# racer2.net
KiCad netlist of a schematic drawn in EAGLE
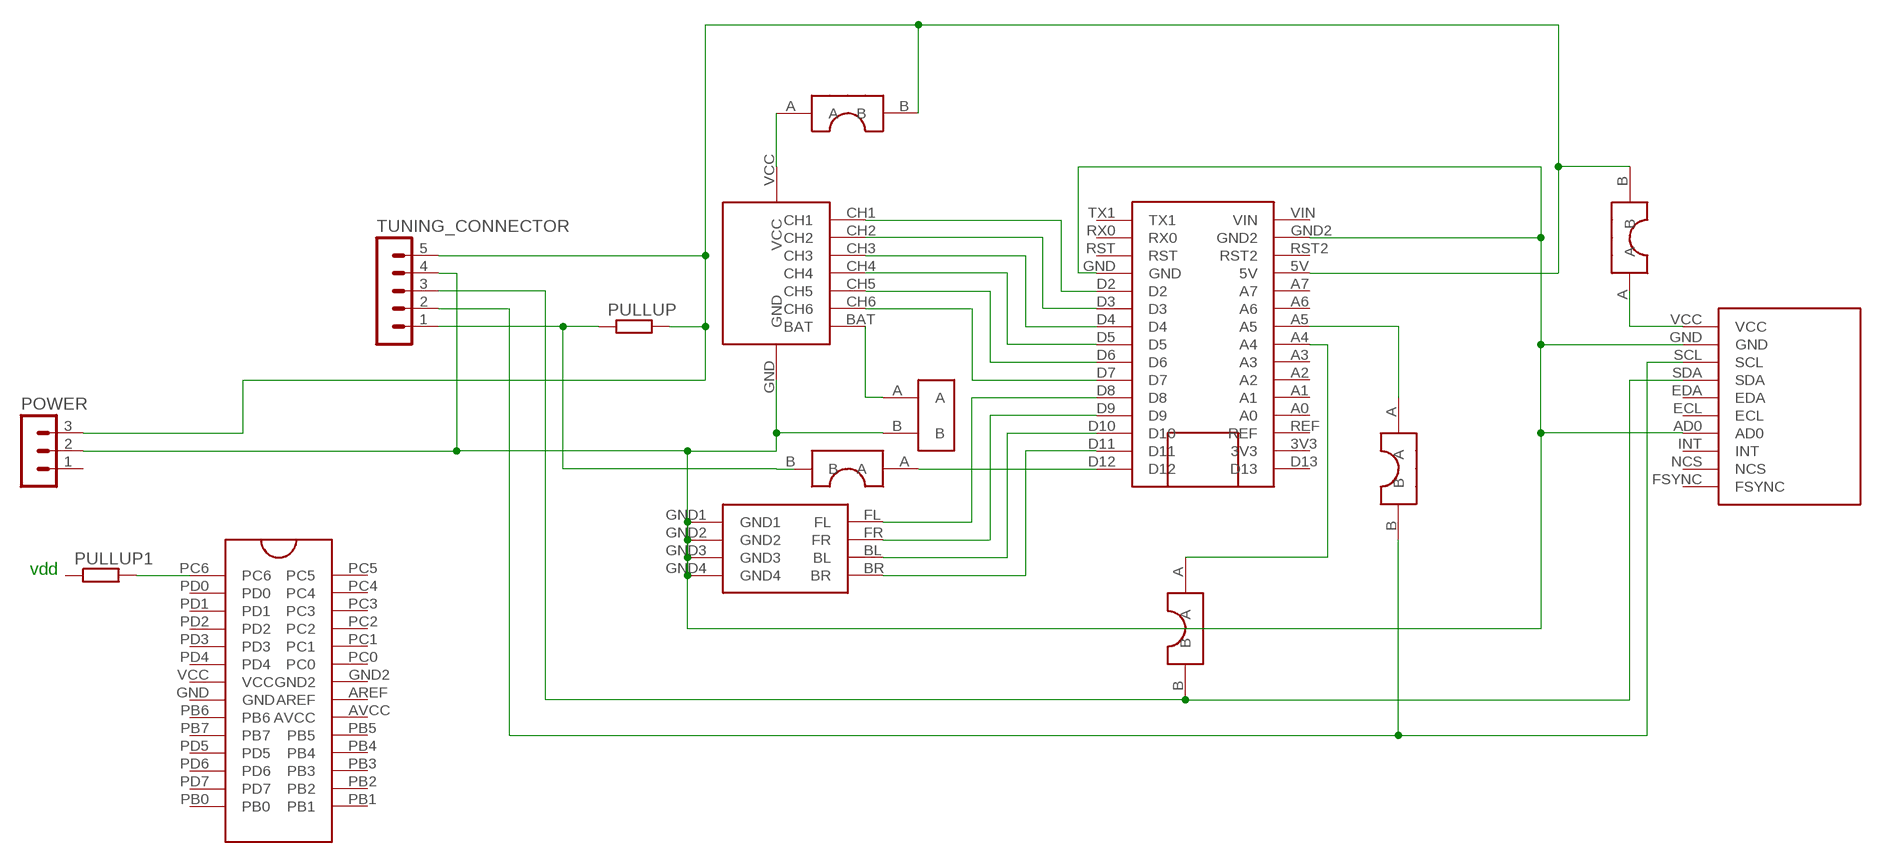
[diagram p0: schematic, sheet 1]

(export (version "E")
  (design (tool "Eeschema 10.0.6"))
  (components
    (comp (ref "POWER")
      (value "MA03-1")
      (footprint "eagle-import:MA03-1")
      (libsource (lib "eagle-import") (part "MA03-1"))
    )
    (comp (ref "PULLUP")
      (value "R0204/7")
      (footprint "eagle-import:0204_7")
      (libsource (lib "eagle-import") (part "R0204/7"))
    )
    (comp (ref "PULLUP1")
      (value "R0204/7")
      (footprint "eagle-import:0204_7")
      (libsource (lib "eagle-import") (part "R0204/7"))
    )
    (comp (ref "TUNING_CONNECTOR")
      (value "MA05-1")
      (footprint "eagle-import:MA05-1")
      (libsource (lib "eagle-import") (part "MA05-1"))
    )
    (comp (ref "U$1")
      (value "NANO")
      (footprint "eagle-import:NANO")
      (libsource (lib "eagle-import") (part "NANO"))
    )
    (comp (ref "U$2")
      (value "BUTTON_PULLUP")
      (footprint "eagle-import:BUTTON_PULLUP")
      (libsource (lib "eagle-import") (part "BUTTON_PULLUP"))
    )
    (comp (ref "U$3")
      (value "FS_RADIO")
      (footprint "eagle-import:FS_RADIO")
      (libsource (lib "eagle-import") (part "FS_RADIO"))
    )
    (comp (ref "U$4")
      (value "MPU9250")
      (footprint "eagle-import:MPU9250")
      (libsource (lib "eagle-import") (part "MPU9250"))
    )
    (comp (ref "U$5")
      (value "MOTOR_HEADER")
      (footprint "eagle-import:MOTOR_HEADER")
      (libsource (lib "eagle-import") (part "MOTOR_HEADER"))
    )
    (comp (ref "U$6")
      (value "BRIDGE")
      (footprint "eagle-import:BRIDGE")
      (libsource (lib "eagle-import") (part "BRIDGE"))
    )
    (comp (ref "U$7")
      (value "BRIDGE")
      (footprint "eagle-import:BRIDGE")
      (libsource (lib "eagle-import") (part "BRIDGE"))
    )
    (comp (ref "U$8")
      (value "BRIDGE")
      (footprint "eagle-import:BRIDGE")
      (libsource (lib "eagle-import") (part "BRIDGE"))
    )
    (comp (ref "U$9")
      (value "BRIDGE")
      (footprint "eagle-import:BRIDGE")
      (libsource (lib "eagle-import") (part "BRIDGE"))
    )
    (comp (ref "U$10")
      (value "BRIDGE")
      (footprint "eagle-import:BRIDGE")
      (libsource (lib "eagle-import") (part "BRIDGE"))
    )
    (comp (ref "U$11")
      (value "ATMEGA328P")
      (footprint "eagle-import:ATMEGA328P")
      (libsource (lib "eagle-import") (part "ATMEGA328P"))
    )
  )
  (nets
    (net (code "1") (name "Net-(POWER-Pad2)") (class "Default")
      (node (ref "POWER") (pin "2") (pinfunction "2_2") (pintype "passive"))
      (node (ref "TUNING_CONNECTOR") (pin "4") (pinfunction "4_4") (pintype "passive"))
      (node (ref "U$1") (pin "GND") (pinfunction "GND_GND") (pintype "bidirectional"))
      (node (ref "U$1") (pin "GND2") (pinfunction "GND2_GND2") (pintype "bidirectional"))
      (node (ref "U$2") (pin "B") (pinfunction "B_B") (pintype "bidirectional"))
      (node (ref "U$3") (pin "GND") (pinfunction "GND_GND") (pintype "bidirectional"))
      (node (ref "U$4") (pin "AD0") (pinfunction "AD0_AD0") (pintype "bidirectional"))
      (node (ref "U$4") (pin "GND") (pinfunction "GND_GND") (pintype "bidirectional"))
      (node (ref "U$5") (pin "GND1") (pinfunction "GND1_GND1") (pintype "bidirectional"))
      (node (ref "U$5") (pin "GND2") (pinfunction "GND2_GND2") (pintype "bidirectional"))
      (node (ref "U$5") (pin "GND3") (pinfunction "GND3_GND3") (pintype "bidirectional"))
      (node (ref "U$5") (pin "GND4") (pinfunction "GND4_GND4") (pintype "bidirectional"))
    )
    (net (code "2") (name "Net-(POWER-Pad3)") (class "Default")
      (node (ref "POWER") (pin "3") (pinfunction "3_3") (pintype "passive"))
      (node (ref "PULLUP") (pin "2") (pinfunction "2_2") (pintype "passive"))
      (node (ref "TUNING_CONNECTOR") (pin "5") (pinfunction "5_5") (pintype "passive"))
      (node (ref "U$1") (pin "5V") (pinfunction "5V_5V") (pintype "bidirectional"))
      (node (ref "U$10") (pin "B") (pinfunction "B_B") (pintype "bidirectional"))
      (node (ref "U$9") (pin "B") (pinfunction "B_B") (pintype "bidirectional"))
    )
    (net (code "3") (name "Net-(PULLUP-Pad1)") (class "Default")
      (node (ref "PULLUP") (pin "1") (pinfunction "1_1") (pintype "passive"))
      (node (ref "TUNING_CONNECTOR") (pin "1") (pinfunction "1_1") (pintype "passive"))
      (node (ref "U$8") (pin "B") (pinfunction "B_B") (pintype "bidirectional"))
    )
    (net (code "4") (name "Net-(PULLUP1-Pad2)") (class "Default")
      (node (ref "PULLUP1") (pin "2") (pinfunction "2_2") (pintype "passive"))
      (node (ref "U$11") (pin "PC6") (pinfunction "PC6_PC6") (pintype "bidirectional"))
    )
    (net (code "5") (name "Net-(TUNING_CONNECTOR-Pad2)") (class "Default")
      (node (ref "TUNING_CONNECTOR") (pin "2") (pinfunction "2_2") (pintype "passive"))
      (node (ref "U$4") (pin "SCL") (pinfunction "SCL_SCL") (pintype "bidirectional"))
      (node (ref "U$7") (pin "B") (pinfunction "B_B") (pintype "bidirectional"))
    )
    (net (code "6") (name "Net-(TUNING_CONNECTOR-Pad3)") (class "Default")
      (node (ref "TUNING_CONNECTOR") (pin "3") (pinfunction "3_3") (pintype "passive"))
      (node (ref "U$4") (pin "SDA") (pinfunction "SDA_SDA") (pintype "bidirectional"))
      (node (ref "U$6") (pin "B") (pinfunction "B_B") (pintype "bidirectional"))
    )
    (net (code "7") (name "Net-(U$1-PadA4)") (class "Default")
      (node (ref "U$1") (pin "A4") (pinfunction "A4_A4") (pintype "bidirectional"))
      (node (ref "U$6") (pin "A") (pinfunction "A_A") (pintype "bidirectional"))
    )
    (net (code "8") (name "Net-(U$1-PadA5)") (class "Default")
      (node (ref "U$1") (pin "A5") (pinfunction "A5_A5") (pintype "bidirectional"))
      (node (ref "U$7") (pin "A") (pinfunction "A_A") (pintype "bidirectional"))
    )
    (net (code "9") (name "Net-(U$1-PadD2)") (class "Default")
      (node (ref "U$1") (pin "D2") (pinfunction "D2_D2") (pintype "bidirectional"))
      (node (ref "U$3") (pin "CH1") (pinfunction "CH1_CH1") (pintype "bidirectional"))
    )
    (net (code "10") (name "Net-(U$1-PadD3)") (class "Default")
      (node (ref "U$1") (pin "D3") (pinfunction "D3_D3") (pintype "bidirectional"))
      (node (ref "U$3") (pin "CH2") (pinfunction "CH2_CH2") (pintype "bidirectional"))
    )
    (net (code "11") (name "Net-(U$1-PadD4)") (class "Default")
      (node (ref "U$1") (pin "D4") (pinfunction "D4_D4") (pintype "bidirectional"))
      (node (ref "U$3") (pin "CH3") (pinfunction "CH3_CH3") (pintype "bidirectional"))
    )
    (net (code "12") (name "Net-(U$1-PadD5)") (class "Default")
      (node (ref "U$1") (pin "D5") (pinfunction "D5_D5") (pintype "bidirectional"))
      (node (ref "U$3") (pin "CH4") (pinfunction "CH4_CH4") (pintype "bidirectional"))
    )
    (net (code "13") (name "Net-(U$1-PadD6)") (class "Default")
      (node (ref "U$1") (pin "D6") (pinfunction "D6_D6") (pintype "bidirectional"))
      (node (ref "U$3") (pin "CH5") (pinfunction "CH5_CH5") (pintype "bidirectional"))
    )
    (net (code "14") (name "Net-(U$1-PadD7)") (class "Default")
      (node (ref "U$1") (pin "D7") (pinfunction "D7_D7") (pintype "bidirectional"))
      (node (ref "U$3") (pin "CH6") (pinfunction "CH6_CH6") (pintype "bidirectional"))
    )
    (net (code "15") (name "Net-(U$1-PadD8)") (class "Default")
      (node (ref "U$1") (pin "D8") (pinfunction "D8_D8") (pintype "bidirectional"))
      (node (ref "U$5") (pin "FL") (pinfunction "FL_FL") (pintype "bidirectional"))
    )
    (net (code "16") (name "Net-(U$1-PadD9)") (class "Default")
      (node (ref "U$1") (pin "D9") (pinfunction "D9_D9") (pintype "bidirectional"))
      (node (ref "U$5") (pin "FR") (pinfunction "FR_FR") (pintype "bidirectional"))
    )
    (net (code "17") (name "Net-(U$1-PadD10)") (class "Default")
      (node (ref "U$1") (pin "D10") (pinfunction "D10_D10") (pintype "bidirectional"))
      (node (ref "U$5") (pin "BL") (pinfunction "BL_BL") (pintype "bidirectional"))
    )
    (net (code "18") (name "Net-(U$1-PadD11)") (class "Default")
      (node (ref "U$1") (pin "D11") (pinfunction "D11_D11") (pintype "bidirectional"))
      (node (ref "U$5") (pin "BR") (pinfunction "BR_BR") (pintype "bidirectional"))
    )
    (net (code "19") (name "Net-(U$1-PadD12)") (class "Default")
      (node (ref "U$1") (pin "D12") (pinfunction "D12_D12") (pintype "bidirectional"))
      (node (ref "U$8") (pin "A") (pinfunction "A_A") (pintype "bidirectional"))
    )
    (net (code "20") (name "Net-(U$2-PadA)") (class "Default")
      (node (ref "U$2") (pin "A") (pinfunction "A_A") (pintype "bidirectional"))
      (node (ref "U$3") (pin "BAT") (pinfunction "BAT_BAT") (pintype "bidirectional"))
    )
    (net (code "21") (name "Net-(U$3-PadVCC)") (class "Default")
      (node (ref "U$3") (pin "VCC") (pinfunction "VCC_VCC") (pintype "bidirectional"))
      (node (ref "U$9") (pin "A") (pinfunction "A_A") (pintype "bidirectional"))
    )
    (net (code "22") (name "Net-(U$10-PadA)") (class "Default")
      (node (ref "U$10") (pin "A") (pinfunction "A_A") (pintype "bidirectional"))
      (node (ref "U$4") (pin "VCC") (pinfunction "VCC_VCC") (pintype "bidirectional"))
    )
    (net (code "23") (name "unconnected-(POWER-Pad1)") (class "Default")
      (node (ref "POWER") (pin "1") (pinfunction "1_1") (pintype "passive"))
    )
    (net (code "24") (name "unconnected-(PULLUP1-Pad1)") (class "Default")
      (node (ref "PULLUP1") (pin "1") (pinfunction "1_1") (pintype "passive"))
    )
    (net (code "25") (name "unconnected-(U$1-Pad3V3)") (class "Default")
      (node (ref "U$1") (pin "3V3") (pinfunction "3V3_3V3") (pintype "bidirectional"))
    )
    (net (code "26") (name "unconnected-(U$1-PadA0)") (class "Default")
      (node (ref "U$1") (pin "A0") (pinfunction "A0_A0") (pintype "bidirectional"))
    )
    (net (code "27") (name "unconnected-(U$1-PadA1)") (class "Default")
      (node (ref "U$1") (pin "A1") (pinfunction "A1_A1") (pintype "bidirectional"))
    )
    (net (code "28") (name "unconnected-(U$1-PadA2)") (class "Default")
      (node (ref "U$1") (pin "A2") (pinfunction "A2_A2") (pintype "bidirectional"))
    )
    (net (code "29") (name "unconnected-(U$1-PadA3)") (class "Default")
      (node (ref "U$1") (pin "A3") (pinfunction "A3_A3") (pintype "bidirectional"))
    )
    (net (code "30") (name "unconnected-(U$1-PadA6)") (class "Default")
      (node (ref "U$1") (pin "A6") (pinfunction "A6_A6") (pintype "bidirectional"))
    )
    (net (code "31") (name "unconnected-(U$1-PadA7)") (class "Default")
      (node (ref "U$1") (pin "A7") (pinfunction "A7_A7") (pintype "bidirectional"))
    )
    (net (code "32") (name "unconnected-(U$1-PadD13)") (class "Default")
      (node (ref "U$1") (pin "D13") (pinfunction "D13_D13") (pintype "bidirectional"))
    )
    (net (code "33") (name "unconnected-(U$1-PadREF)") (class "Default")
      (node (ref "U$1") (pin "REF") (pinfunction "REF_REF") (pintype "bidirectional"))
    )
    (net (code "34") (name "unconnected-(U$1-PadRST)") (class "Default")
      (node (ref "U$1") (pin "RST") (pinfunction "RST_RST") (pintype "bidirectional"))
    )
    (net (code "35") (name "unconnected-(U$1-PadRST2)") (class "Default")
      (node (ref "U$1") (pin "RST2") (pinfunction "RST2_RST2") (pintype "bidirectional"))
    )
    (net (code "36") (name "unconnected-(U$1-PadRX0)") (class "Default")
      (node (ref "U$1") (pin "RX0") (pinfunction "RX0_RX0") (pintype "bidirectional"))
    )
    (net (code "37") (name "unconnected-(U$1-PadTX1)") (class "Default")
      (node (ref "U$1") (pin "TX1") (pinfunction "TX1_TX1") (pintype "bidirectional"))
    )
    (net (code "38") (name "unconnected-(U$1-PadVIN)") (class "Default")
      (node (ref "U$1") (pin "VIN") (pinfunction "VIN_VIN") (pintype "bidirectional"))
    )
    (net (code "39") (name "unconnected-(U$4-PadECL)") (class "Default")
      (node (ref "U$4") (pin "ECL") (pinfunction "ECL_ECL") (pintype "bidirectional"))
    )
    (net (code "40") (name "unconnected-(U$4-PadEDA)") (class "Default")
      (node (ref "U$4") (pin "EDA") (pinfunction "EDA_EDA") (pintype "bidirectional"))
    )
    (net (code "41") (name "unconnected-(U$4-PadFSYNC)") (class "Default")
      (node (ref "U$4") (pin "FSYNC") (pinfunction "FSYNC_FSYNC") (pintype "bidirectional"))
    )
    (net (code "42") (name "unconnected-(U$4-PadINT)") (class "Default")
      (node (ref "U$4") (pin "INT") (pinfunction "INT_INT") (pintype "bidirectional"))
    )
    (net (code "43") (name "unconnected-(U$4-PadNCS)") (class "Default")
      (node (ref "U$4") (pin "NCS") (pinfunction "NCS_NCS") (pintype "bidirectional"))
    )
    (net (code "44") (name "unconnected-(U$11-PadAREF)") (class "Default")
      (node (ref "U$11") (pin "AREF") (pinfunction "AREF_AREF") (pintype "bidirectional"))
    )
    (net (code "45") (name "unconnected-(U$11-PadAVCC)") (class "Default")
      (node (ref "U$11") (pin "AVCC") (pinfunction "AVCC_AVCC") (pintype "bidirectional"))
    )
    (net (code "46") (name "unconnected-(U$11-PadGND)") (class "Default")
      (node (ref "U$11") (pin "GND") (pinfunction "GND_GND") (pintype "bidirectional"))
    )
    (net (code "47") (name "unconnected-(U$11-PadGND2)") (class "Default")
      (node (ref "U$11") (pin "GND2") (pinfunction "GND2_GND2") (pintype "bidirectional"))
    )
    (net (code "48") (name "unconnected-(U$11-PadPB0)") (class "Default")
      (node (ref "U$11") (pin "PB0") (pinfunction "PB0_PB0") (pintype "bidirectional"))
    )
    (net (code "49") (name "unconnected-(U$11-PadPB1)") (class "Default")
      (node (ref "U$11") (pin "PB1") (pinfunction "PB1_PB1") (pintype "bidirectional"))
    )
    (net (code "50") (name "unconnected-(U$11-PadPB2)") (class "Default")
      (node (ref "U$11") (pin "PB2") (pinfunction "PB2_PB2") (pintype "bidirectional"))
    )
    (net (code "51") (name "unconnected-(U$11-PadPB3)") (class "Default")
      (node (ref "U$11") (pin "PB3") (pinfunction "PB3_PB3") (pintype "bidirectional"))
    )
    (net (code "52") (name "unconnected-(U$11-PadPB4)") (class "Default")
      (node (ref "U$11") (pin "PB4") (pinfunction "PB4_PB4") (pintype "bidirectional"))
    )
    (net (code "53") (name "unconnected-(U$11-PadPB5)") (class "Default")
      (node (ref "U$11") (pin "PB5") (pinfunction "PB5_PB5") (pintype "bidirectional"))
    )
    (net (code "54") (name "unconnected-(U$11-PadPB6)") (class "Default")
      (node (ref "U$11") (pin "PB6") (pinfunction "PB6_PB6") (pintype "bidirectional"))
    )
    (net (code "55") (name "unconnected-(U$11-PadPB7)") (class "Default")
      (node (ref "U$11") (pin "PB7") (pinfunction "PB7_PB7") (pintype "bidirectional"))
    )
    (net (code "56") (name "unconnected-(U$11-PadPC0)") (class "Default")
      (node (ref "U$11") (pin "PC0") (pinfunction "PC0_PC0") (pintype "bidirectional"))
    )
    (net (code "57") (name "unconnected-(U$11-PadPC1)") (class "Default")
      (node (ref "U$11") (pin "PC1") (pinfunction "PC1_PC1") (pintype "bidirectional"))
    )
    (net (code "58") (name "unconnected-(U$11-PadPC2)") (class "Default")
      (node (ref "U$11") (pin "PC2") (pinfunction "PC2_PC2") (pintype "bidirectional"))
    )
    (net (code "59") (name "unconnected-(U$11-PadPC3)") (class "Default")
      (node (ref "U$11") (pin "PC3") (pinfunction "PC3_PC3") (pintype "bidirectional"))
    )
    (net (code "60") (name "unconnected-(U$11-PadPC4)") (class "Default")
      (node (ref "U$11") (pin "PC4") (pinfunction "PC4_PC4") (pintype "bidirectional"))
    )
    (net (code "61") (name "unconnected-(U$11-PadPC5)") (class "Default")
      (node (ref "U$11") (pin "PC5") (pinfunction "PC5_PC5") (pintype "bidirectional"))
    )
    (net (code "62") (name "unconnected-(U$11-PadPD0)") (class "Default")
      (node (ref "U$11") (pin "PD0") (pinfunction "PD0_PD0") (pintype "bidirectional"))
    )
    (net (code "63") (name "unconnected-(U$11-PadPD1)") (class "Default")
      (node (ref "U$11") (pin "PD1") (pinfunction "PD1_PD1") (pintype "bidirectional"))
    )
    (net (code "64") (name "unconnected-(U$11-PadPD2)") (class "Default")
      (node (ref "U$11") (pin "PD2") (pinfunction "PD2_PD2") (pintype "bidirectional"))
    )
    (net (code "65") (name "unconnected-(U$11-PadPD3)") (class "Default")
      (node (ref "U$11") (pin "PD3") (pinfunction "PD3_PD3") (pintype "bidirectional"))
    )
    (net (code "66") (name "unconnected-(U$11-PadPD4)") (class "Default")
      (node (ref "U$11") (pin "PD4") (pinfunction "PD4_PD4") (pintype "bidirectional"))
    )
    (net (code "67") (name "unconnected-(U$11-PadPD5)") (class "Default")
      (node (ref "U$11") (pin "PD5") (pinfunction "PD5_PD5") (pintype "bidirectional"))
    )
    (net (code "68") (name "unconnected-(U$11-PadPD6)") (class "Default")
      (node (ref "U$11") (pin "PD6") (pinfunction "PD6_PD6") (pintype "bidirectional"))
    )
    (net (code "69") (name "unconnected-(U$11-PadPD7)") (class "Default")
      (node (ref "U$11") (pin "PD7") (pinfunction "PD7_PD7") (pintype "bidirectional"))
    )
    (net (code "70") (name "unconnected-(U$11-PadVCC)") (class "Default")
      (node (ref "U$11") (pin "VCC") (pinfunction "VCC_VCC") (pintype "bidirectional"))
    )
  )
)
